# trafficlight.net
KiCad netlist of a schematic drawn in Altium Designer
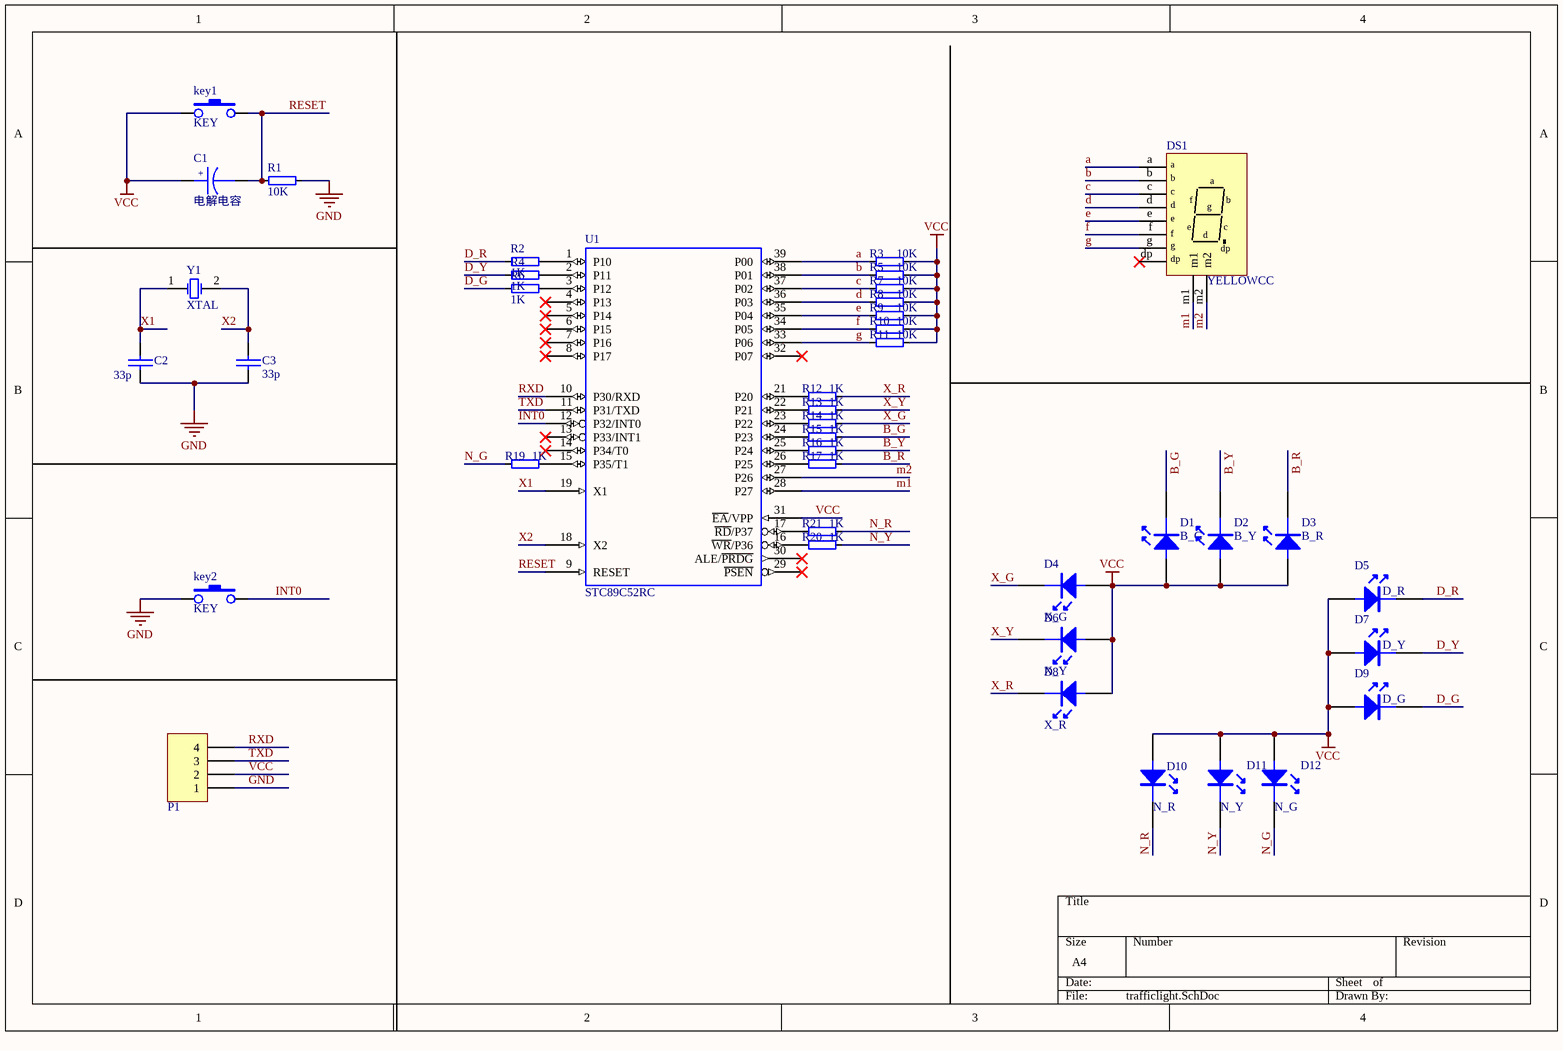
[diagram p0: trafficlight.SchDoc]

(export (version "E")
  (design (tool "Eeschema 10.0.6"))
  (components
    (comp (ref "C1")
      (value "电解电容")
      (footprint "D50V10UF")
      (description "Capacitor")
      (libsource (lib "trafficlight") (part "电解电容"))
    )
    (comp (ref "C2")
      (value "33p")
      (footprint "D104")
      (description "Capacitor")
      (libsource (lib "trafficlight") (part "普通电容"))
    )
    (comp (ref "C3")
      (value "33p")
      (footprint "D104")
      (description "Capacitor")
      (libsource (lib "trafficlight") (part "普通电容"))
    )
    (comp (ref "D1") (value "B_G") (footprint "LED") (libsource (lib "trafficlight") (part "LED")))
    (comp (ref "D2") (value "B_Y") (footprint "LED") (libsource (lib "trafficlight") (part "LED")))
    (comp (ref "D3") (value "B_R") (footprint "LED") (libsource (lib "trafficlight") (part "LED")))
    (comp (ref "D4") (value "X_G") (footprint "LED") (libsource (lib "trafficlight") (part "LED")))
    (comp (ref "D5") (value "D_R") (footprint "LED") (libsource (lib "trafficlight") (part "LED")))
    (comp (ref "D6") (value "X_Y") (footprint "LED") (libsource (lib "trafficlight") (part "LED")))
    (comp (ref "D7") (value "D_Y") (footprint "LED") (libsource (lib "trafficlight") (part "LED")))
    (comp (ref "D8") (value "X_R") (footprint "LED") (libsource (lib "trafficlight") (part "LED")))
    (comp (ref "D9") (value "D_G") (footprint "LED") (libsource (lib "trafficlight") (part "LED")))
    (comp (ref "D10") (value "N_R") (footprint "LED") (libsource (lib "trafficlight") (part "LED")))
    (comp (ref "D11") (value "N_Y") (footprint "LED") (libsource (lib "trafficlight") (part "LED")))
    (comp (ref "D12") (value "N_G") (footprint "LED") (libsource (lib "trafficlight") (part "LED")))
    (comp (ref "DS1")
      (value "YELLOWCC")
      (footprint "0.5INCH-DISP")
      (description "Common Cathhode Seven-Segment Display, Right Hand Decimal")
      (libsource (lib "trafficlight") (part "YELLOWCC"))
    )
    (comp (ref "key1") (value "KEY") (footprint "6X6X?") (libsource (lib "trafficlight") (part "KEY")))
    (comp (ref "key2") (value "KEY") (footprint "6X6X?") (libsource (lib "trafficlight") (part "KEY")))
    (comp (ref "P1")
      (value "Header 4")
      (footprint "SIP4")
      (description "Header, 4-Pin")
      (fields (field (name "PUBLISHER") "Altium Limited"))
      (libsource (lib "trafficlight") (part "Header 4"))
    )
    (comp (ref "R1") (value "10K") (footprint "AXIAL0.4") (libsource (lib "trafficlight") (part "RES")))
    (comp (ref "R2") (value "1K") (footprint "AXIAL0.4") (libsource (lib "trafficlight") (part "RES")))
    (comp (ref "R3") (value "10K") (footprint "AXIAL0.4") (libsource (lib "trafficlight") (part "RES")))
    (comp (ref "R4") (value "1K") (footprint "AXIAL0.4") (libsource (lib "trafficlight") (part "RES")))
    (comp (ref "R5") (value "10K") (footprint "AXIAL0.4") (libsource (lib "trafficlight") (part "RES")))
    (comp (ref "R6") (value "1K") (footprint "AXIAL0.4") (libsource (lib "trafficlight") (part "RES")))
    (comp (ref "R7") (value "10K") (footprint "AXIAL0.4") (libsource (lib "trafficlight") (part "RES")))
    (comp (ref "R8") (value "10K") (footprint "AXIAL0.4") (libsource (lib "trafficlight") (part "RES")))
    (comp (ref "R9") (value "10K") (footprint "AXIAL0.4") (libsource (lib "trafficlight") (part "RES")))
    (comp (ref "R10") (value "10K") (footprint "AXIAL0.4") (libsource (lib "trafficlight") (part "RES")))
    (comp (ref "R11") (value "10K") (footprint "AXIAL0.4") (libsource (lib "trafficlight") (part "RES")))
    (comp (ref "R12") (value "1K") (footprint "AXIAL0.4") (libsource (lib "trafficlight") (part "RES")))
    (comp (ref "R13") (value "1K") (footprint "AXIAL0.4") (libsource (lib "trafficlight") (part "RES")))
    (comp (ref "R14") (value "1K") (footprint "AXIAL0.4") (libsource (lib "trafficlight") (part "RES")))
    (comp (ref "R15") (value "1K") (footprint "AXIAL0.4") (libsource (lib "trafficlight") (part "RES")))
    (comp (ref "R16") (value "1K") (footprint "AXIAL0.4") (libsource (lib "trafficlight") (part "RES")))
    (comp (ref "R17") (value "1K") (footprint "AXIAL0.4") (libsource (lib "trafficlight") (part "RES")))
    (comp (ref "R19") (value "1K") (footprint "AXIAL0.4") (libsource (lib "trafficlight") (part "RES")))
    (comp (ref "R20") (value "1K") (footprint "AXIAL0.4") (libsource (lib "trafficlight") (part "RES")))
    (comp (ref "R21") (value "1K") (footprint "AXIAL0.4") (libsource (lib "trafficlight") (part "RES")))
    (comp (ref "U1")
      (value "STC89C52RC")
      (footprint "DIP40C")
      (libsource (lib "trafficlight") (part "AT89C51"))
    )
    (comp (ref "Y1") (value "XTAL") (footprint "晶振") (libsource (lib "trafficlight") (part "XTAL")))
  )
  (nets
    (net (code "1") (name "/B_G") (class "Default")
      (node (ref "D1") (pin "2") (pinfunction "2_2") (pintype "passive"))
      (node (ref "R15") (pin "2") (pinfunction "2_2") (pintype "passive"))
    )
    (net (code "2") (name "/B_R") (class "Default")
      (node (ref "D3") (pin "2") (pinfunction "2_2") (pintype "passive"))
      (node (ref "R17") (pin "2") (pinfunction "2_2") (pintype "passive"))
    )
    (net (code "3") (name "/B_Y") (class "Default")
      (node (ref "D2") (pin "2") (pinfunction "2_2") (pintype "passive"))
      (node (ref "R16") (pin "2") (pinfunction "2_2") (pintype "passive"))
    )
    (net (code "4") (name "/D_G") (class "Default")
      (node (ref "D9") (pin "2") (pinfunction "2_2") (pintype "passive"))
      (node (ref "R6") (pin "2") (pinfunction "2_2") (pintype "passive"))
    )
    (net (code "5") (name "/D_R") (class "Default")
      (node (ref "D5") (pin "2") (pinfunction "2_2") (pintype "passive"))
      (node (ref "R2") (pin "2") (pinfunction "2_2") (pintype "passive"))
    )
    (net (code "6") (name "/D_Y") (class "Default")
      (node (ref "D7") (pin "2") (pinfunction "2_2") (pintype "passive"))
      (node (ref "R4") (pin "2") (pinfunction "2_2") (pintype "passive"))
    )
    (net (code "7") (name "/INT0") (class "Default")
      (node (ref "U1") (pin "12") (pinfunction "P32/INT0_12") (pintype "bidirectional"))
      (node (ref "key2") (pin "2") (pinfunction "2_2") (pintype "passive"))
    )
    (net (code "8") (name "/N_G") (class "Default")
      (node (ref "D12") (pin "2") (pinfunction "2_2") (pintype "passive"))
      (node (ref "R19") (pin "1") (pinfunction "1_1") (pintype "passive"))
    )
    (net (code "9") (name "/N_R") (class "Default")
      (node (ref "D10") (pin "2") (pinfunction "2_2") (pintype "passive"))
      (node (ref "R21") (pin "2") (pinfunction "2_2") (pintype "passive"))
    )
    (net (code "10") (name "/N_Y") (class "Default")
      (node (ref "D11") (pin "2") (pinfunction "2_2") (pintype "passive"))
      (node (ref "R20") (pin "2") (pinfunction "2_2") (pintype "passive"))
    )
    (net (code "11") (name "/RESET") (class "Default")
      (node (ref "C1") (pin "2") (pinfunction "2_2") (pintype "passive"))
      (node (ref "R1") (pin "1") (pinfunction "1_1") (pintype "passive"))
      (node (ref "U1") (pin "9") (pinfunction "RESET_9") (pintype "input"))
      (node (ref "key1") (pin "2") (pinfunction "2_2") (pintype "passive"))
    )
    (net (code "12") (name "/RXD") (class "Default")
      (node (ref "P1") (pin "4") (pinfunction "4_4") (pintype "passive"))
      (node (ref "U1") (pin "10") (pinfunction "P30/RXD_10") (pintype "bidirectional"))
    )
    (net (code "13") (name "/TXD") (class "Default")
      (node (ref "P1") (pin "3") (pinfunction "3_3") (pintype "passive"))
      (node (ref "U1") (pin "11") (pinfunction "P31/TXD_11") (pintype "bidirectional"))
    )
    (net (code "14") (name "/X1") (class "Default")
      (node (ref "C2") (pin "1") (pinfunction "1_1") (pintype "passive"))
      (node (ref "U1") (pin "19") (pinfunction "X1_19") (pintype "input"))
      (node (ref "Y1") (pin "1") (pinfunction "1_1") (pintype "passive"))
    )
    (net (code "15") (name "/X2") (class "Default")
      (node (ref "C3") (pin "1") (pinfunction "1_1") (pintype "passive"))
      (node (ref "U1") (pin "18") (pinfunction "X2_18") (pintype "input"))
      (node (ref "Y1") (pin "2") (pinfunction "2_2") (pintype "passive"))
    )
    (net (code "16") (name "/X_G") (class "Default")
      (node (ref "D4") (pin "2") (pinfunction "2_2") (pintype "passive"))
      (node (ref "R14") (pin "2") (pinfunction "2_2") (pintype "passive"))
    )
    (net (code "17") (name "/X_R") (class "Default")
      (node (ref "D8") (pin "2") (pinfunction "2_2") (pintype "passive"))
      (node (ref "R12") (pin "2") (pinfunction "2_2") (pintype "passive"))
    )
    (net (code "18") (name "/X_Y") (class "Default")
      (node (ref "D6") (pin "2") (pinfunction "2_2") (pintype "passive"))
      (node (ref "R13") (pin "2") (pinfunction "2_2") (pintype "passive"))
    )
    (net (code "19") (name "/a") (class "Default")
      (node (ref "DS1") (pin "a") (pinfunction "a_a") (pintype "passive"))
      (node (ref "R3") (pin "1") (pinfunction "1_1") (pintype "passive"))
      (node (ref "U1") (pin "39") (pinfunction "P00_39") (pintype "bidirectional"))
    )
    (net (code "20") (name "/b") (class "Default")
      (node (ref "DS1") (pin "b") (pinfunction "b_b") (pintype "passive"))
      (node (ref "R5") (pin "1") (pinfunction "1_1") (pintype "passive"))
      (node (ref "U1") (pin "38") (pinfunction "P01_38") (pintype "bidirectional"))
    )
    (net (code "21") (name "/c") (class "Default")
      (node (ref "DS1") (pin "c") (pinfunction "c_c") (pintype "passive"))
      (node (ref "R7") (pin "1") (pinfunction "1_1") (pintype "passive"))
      (node (ref "U1") (pin "37") (pinfunction "P02_37") (pintype "bidirectional"))
    )
    (net (code "22") (name "/d") (class "Default")
      (node (ref "DS1") (pin "d") (pinfunction "d_d") (pintype "passive"))
      (node (ref "R8") (pin "1") (pinfunction "1_1") (pintype "passive"))
      (node (ref "U1") (pin "36") (pinfunction "P03_36") (pintype "bidirectional"))
    )
    (net (code "23") (name "/e") (class "Default")
      (node (ref "DS1") (pin "e") (pinfunction "e_e") (pintype "passive"))
      (node (ref "R9") (pin "1") (pinfunction "1_1") (pintype "passive"))
      (node (ref "U1") (pin "35") (pinfunction "P04_35") (pintype "bidirectional"))
    )
    (net (code "24") (name "/f") (class "Default")
      (node (ref "DS1") (pin "f") (pinfunction "f_f") (pintype "passive"))
      (node (ref "R10") (pin "1") (pinfunction "1_1") (pintype "passive"))
      (node (ref "U1") (pin "34") (pinfunction "P05_34") (pintype "bidirectional"))
    )
    (net (code "25") (name "/g") (class "Default")
      (node (ref "DS1") (pin "g") (pinfunction "g_g") (pintype "passive"))
      (node (ref "R11") (pin "1") (pinfunction "1_1") (pintype "passive"))
      (node (ref "U1") (pin "33") (pinfunction "P06_33") (pintype "bidirectional"))
    )
    (net (code "26") (name "/m1") (class "Default")
      (node (ref "DS1") (pin "m1") (pinfunction "m1_m1") (pintype "passive"))
      (node (ref "U1") (pin "28") (pinfunction "P27_28") (pintype "bidirectional"))
    )
    (net (code "27") (name "/m2") (class "Default")
      (node (ref "DS1") (pin "m2") (pinfunction "m2_m2") (pintype "passive"))
      (node (ref "U1") (pin "27") (pinfunction "P26_27") (pintype "bidirectional"))
    )
    (net (code "28") (name "GND") (class "Default")
      (node (ref "C2") (pin "2") (pinfunction "2_2") (pintype "passive"))
      (node (ref "C3") (pin "2") (pinfunction "2_2") (pintype "passive"))
      (node (ref "P1") (pin "1") (pinfunction "1_1") (pintype "passive"))
      (node (ref "R1") (pin "2") (pinfunction "2_2") (pintype "passive"))
      (node (ref "U1") (pin "20") (pinfunction "GND_20") (pintype "power_in"))
      (node (ref "key2") (pin "1") (pinfunction "1_1") (pintype "passive"))
    )
    (net (code "29") (name "Net-(U1-P10)") (class "Default")
      (node (ref "R2") (pin "1") (pinfunction "1_1") (pintype "passive"))
      (node (ref "U1") (pin "1") (pinfunction "P10_1") (pintype "bidirectional"))
    )
    (net (code "30") (name "Net-(U1-P11)") (class "Default")
      (node (ref "R4") (pin "1") (pinfunction "1_1") (pintype "passive"))
      (node (ref "U1") (pin "2") (pinfunction "P11_2") (pintype "bidirectional"))
    )
    (net (code "31") (name "Net-(U1-P12)") (class "Default")
      (node (ref "R6") (pin "1") (pinfunction "1_1") (pintype "passive"))
      (node (ref "U1") (pin "3") (pinfunction "P12_3") (pintype "bidirectional"))
    )
    (net (code "32") (name "Net-(U1-P20)") (class "Default")
      (node (ref "R12") (pin "1") (pinfunction "1_1") (pintype "passive"))
      (node (ref "U1") (pin "21") (pinfunction "P20_21") (pintype "bidirectional"))
    )
    (net (code "33") (name "Net-(U1-P21)") (class "Default")
      (node (ref "R13") (pin "1") (pinfunction "1_1") (pintype "passive"))
      (node (ref "U1") (pin "22") (pinfunction "P21_22") (pintype "bidirectional"))
    )
    (net (code "34") (name "Net-(U1-P22)") (class "Default")
      (node (ref "R14") (pin "1") (pinfunction "1_1") (pintype "passive"))
      (node (ref "U1") (pin "23") (pinfunction "P22_23") (pintype "bidirectional"))
    )
    (net (code "35") (name "Net-(U1-P23)") (class "Default")
      (node (ref "R15") (pin "1") (pinfunction "1_1") (pintype "passive"))
      (node (ref "U1") (pin "24") (pinfunction "P23_24") (pintype "bidirectional"))
    )
    (net (code "36") (name "Net-(U1-P24)") (class "Default")
      (node (ref "R16") (pin "1") (pinfunction "1_1") (pintype "passive"))
      (node (ref "U1") (pin "25") (pinfunction "P24_25") (pintype "bidirectional"))
    )
    (net (code "37") (name "Net-(U1-P25)") (class "Default")
      (node (ref "R17") (pin "1") (pinfunction "1_1") (pintype "passive"))
      (node (ref "U1") (pin "26") (pinfunction "P25_26") (pintype "bidirectional"))
    )
    (net (code "38") (name "Net-(U1-P35{slash}T1)") (class "Default")
      (node (ref "R19") (pin "2") (pinfunction "2_2") (pintype "passive"))
      (node (ref "U1") (pin "15") (pinfunction "P35/T1_15") (pintype "bidirectional"))
    )
    (net (code "39") (name "Net-(U1-~{RD}{slash}P37)") (class "Default")
      (node (ref "R21") (pin "1") (pinfunction "1_1") (pintype "passive"))
      (node (ref "U1") (pin "17") (pinfunction "~{RD}/P37_17") (pintype "bidirectional"))
    )
    (net (code "40") (name "Net-(U1-~{WR}{slash}P36)") (class "Default")
      (node (ref "R20") (pin "1") (pinfunction "1_1") (pintype "passive"))
      (node (ref "U1") (pin "16") (pinfunction "~{WR}/P36_16") (pintype "bidirectional"))
    )
    (net (code "41") (name "VCC") (class "Default")
      (node (ref "C1") (pin "1") (pinfunction "1_1") (pintype "passive"))
      (node (ref "D1") (pin "1") (pinfunction "1_1") (pintype "passive"))
      (node (ref "D10") (pin "1") (pinfunction "1_1") (pintype "passive"))
      (node (ref "D11") (pin "1") (pinfunction "1_1") (pintype "passive"))
      (node (ref "D12") (pin "1") (pinfunction "1_1") (pintype "passive"))
      (node (ref "D2") (pin "1") (pinfunction "1_1") (pintype "passive"))
      (node (ref "D3") (pin "1") (pinfunction "1_1") (pintype "passive"))
      (node (ref "D4") (pin "1") (pinfunction "1_1") (pintype "passive"))
      (node (ref "D5") (pin "1") (pinfunction "1_1") (pintype "passive"))
      (node (ref "D6") (pin "1") (pinfunction "1_1") (pintype "passive"))
      (node (ref "D7") (pin "1") (pinfunction "1_1") (pintype "passive"))
      (node (ref "D8") (pin "1") (pinfunction "1_1") (pintype "passive"))
      (node (ref "D9") (pin "1") (pinfunction "1_1") (pintype "passive"))
      (node (ref "P1") (pin "2") (pinfunction "2_2") (pintype "passive"))
      (node (ref "R10") (pin "2") (pinfunction "2_2") (pintype "passive"))
      (node (ref "R11") (pin "2") (pinfunction "2_2") (pintype "passive"))
      (node (ref "R3") (pin "2") (pinfunction "2_2") (pintype "passive"))
      (node (ref "R5") (pin "2") (pinfunction "2_2") (pintype "passive"))
      (node (ref "R7") (pin "2") (pinfunction "2_2") (pintype "passive"))
      (node (ref "R8") (pin "2") (pinfunction "2_2") (pintype "passive"))
      (node (ref "R9") (pin "2") (pinfunction "2_2") (pintype "passive"))
      (node (ref "U1") (pin "31") (pinfunction "~{EA}/VPP_31") (pintype "input"))
      (node (ref "U1") (pin "40") (pinfunction "VCC_40") (pintype "power_in"))
      (node (ref "key1") (pin "1") (pinfunction "1_1") (pintype "passive"))
    )
    (net (code "42") (name "unconnected-(DS1-Paddp)") (class "Default")
      (node (ref "DS1") (pin "dp") (pinfunction "dp_dp") (pintype "passive+no_connect"))
    )
    (net (code "43") (name "unconnected-(U1-ALE{slash}~{PRDG}-Pad30)") (class "Default")
      (node (ref "U1") (pin "30") (pinfunction "ALE/~{PRDG}_30") (pintype "output+no_connect"))
    )
    (net (code "44") (name "unconnected-(U1-P07-Pad32)") (class "Default")
      (node (ref "U1") (pin "32") (pinfunction "P07_32") (pintype "bidirectional+no_connect"))
    )
    (net (code "45") (name "unconnected-(U1-P13-Pad4)") (class "Default")
      (node (ref "U1") (pin "4") (pinfunction "P13_4") (pintype "bidirectional+no_connect"))
    )
    (net (code "46") (name "unconnected-(U1-P14-Pad5)") (class "Default")
      (node (ref "U1") (pin "5") (pinfunction "P14_5") (pintype "bidirectional+no_connect"))
    )
    (net (code "47") (name "unconnected-(U1-P15-Pad6)") (class "Default")
      (node (ref "U1") (pin "6") (pinfunction "P15_6") (pintype "bidirectional+no_connect"))
    )
    (net (code "48") (name "unconnected-(U1-P16-Pad7)") (class "Default")
      (node (ref "U1") (pin "7") (pinfunction "P16_7") (pintype "bidirectional+no_connect"))
    )
    (net (code "49") (name "unconnected-(U1-P17-Pad8)") (class "Default")
      (node (ref "U1") (pin "8") (pinfunction "P17_8") (pintype "bidirectional+no_connect"))
    )
    (net (code "50") (name "unconnected-(U1-P33{slash}INT1-Pad13)") (class "Default")
      (node (ref "U1") (pin "13") (pinfunction "P33/INT1_13") (pintype "bidirectional+no_connect"))
    )
    (net (code "51") (name "unconnected-(U1-P34{slash}T0-Pad14)") (class "Default")
      (node (ref "U1") (pin "14") (pinfunction "P34/T0_14") (pintype "bidirectional+no_connect"))
    )
    (net (code "52") (name "unconnected-(U1-~{PSEN}-Pad29)") (class "Default")
      (node (ref "U1") (pin "29") (pinfunction "~{PSEN}_29") (pintype "output+no_connect"))
    )
  )
)
